# TMS1_2025_NOT_INVERTED.net
KiCad netlist of a schematic drawn in EasyEDA
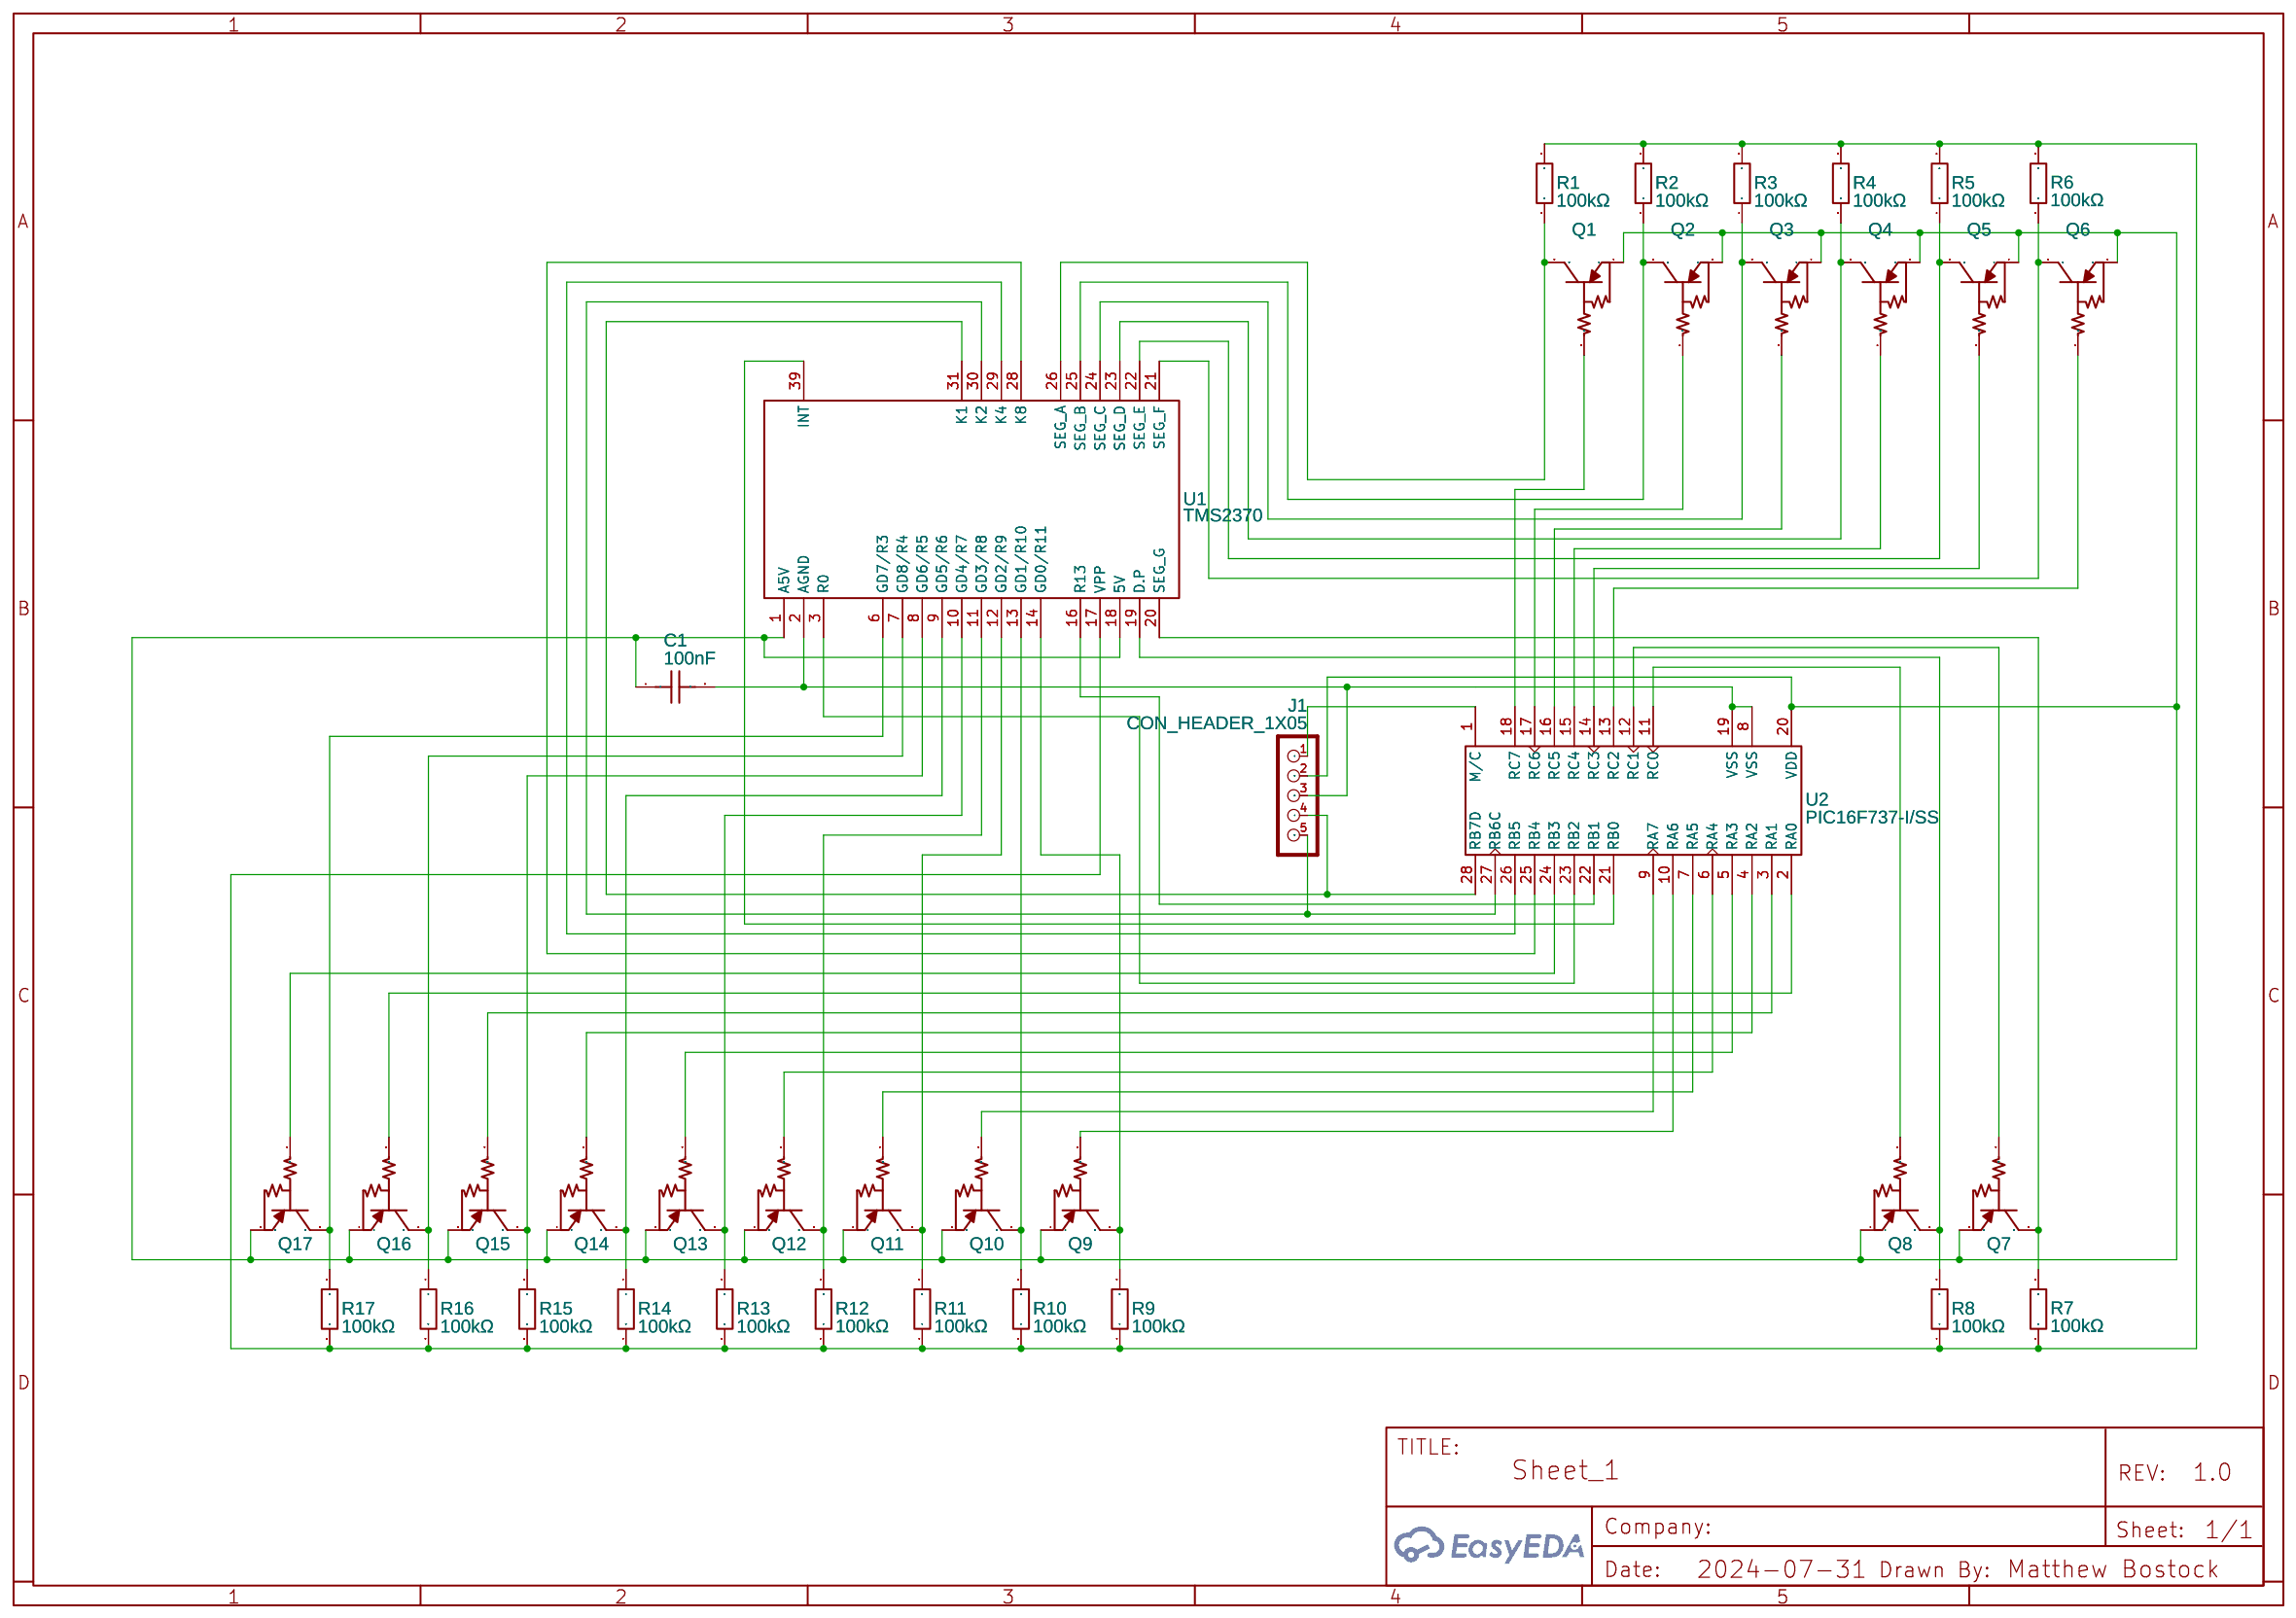
[diagram p0: schematic sheet]

(export (version "E")
  (design (tool "Eeschema 10.0.6"))
  (components
    (comp (ref "C1")
      (value "100nF")
      (fields
        (field (name "Manufacturer Part") "CC0603KRX7R9BB104")
        (field (name "Manufacturer") "YAGEO(国巨)")
      )
      (libsource (lib "") (part "CC0603KRX7R9BB104"))
    )
    (comp (ref "J1") (value "CON_HEADER_1X05") (libsource (lib "") (part "CON_HEADER_1X05")))
    (comp (ref "Q1")
      (value "DTB113ZKT146_SLIM")
      (fields (field (name "Manufacturer Part") "DTB113ZKT146") (field (name "Manufacturer") "ROHM(罗姆)"))
      (libsource (lib "") (part "DTB113ZKT146_SLIM"))
    )
    (comp (ref "Q2")
      (value "DTB113ZKT146_SLIM")
      (fields (field (name "Manufacturer Part") "DTB113ZKT146") (field (name "Manufacturer") "ROHM(罗姆)"))
      (libsource (lib "") (part "DTB113ZKT146_SLIM"))
    )
    (comp (ref "Q3")
      (value "DTB113ZKT146_SLIM")
      (fields (field (name "Manufacturer Part") "DTB113ZKT146") (field (name "Manufacturer") "ROHM(罗姆)"))
      (libsource (lib "") (part "DTB113ZKT146_SLIM"))
    )
    (comp (ref "Q4")
      (value "DTB113ZKT146_SLIM")
      (fields (field (name "Manufacturer Part") "DTB113ZKT146") (field (name "Manufacturer") "ROHM(罗姆)"))
      (libsource (lib "") (part "DTB113ZKT146_SLIM"))
    )
    (comp (ref "Q5")
      (value "DTB113ZKT146_SLIM")
      (fields (field (name "Manufacturer Part") "DTB113ZKT146") (field (name "Manufacturer") "ROHM(罗姆)"))
      (libsource (lib "") (part "DTB113ZKT146_SLIM"))
    )
    (comp (ref "Q6")
      (value "DTB113ZKT146_SLIM")
      (fields (field (name "Manufacturer Part") "DTB113ZKT146") (field (name "Manufacturer") "ROHM(罗姆)"))
      (libsource (lib "") (part "DTB113ZKT146_SLIM"))
    )
    (comp (ref "Q7")
      (value "DTB113ZKT146_SLIM")
      (fields (field (name "Manufacturer Part") "DTB113ZKT146") (field (name "Manufacturer") "ROHM(罗姆)"))
      (libsource (lib "") (part "DTB113ZKT146_SLIM_1"))
    )
    (comp (ref "Q8")
      (value "DTB113ZKT146_SLIM")
      (fields (field (name "Manufacturer Part") "DTB113ZKT146") (field (name "Manufacturer") "ROHM(罗姆)"))
      (libsource (lib "") (part "DTB113ZKT146_SLIM_1"))
    )
    (comp (ref "Q9")
      (value "DTB113ZKT146_SLIM")
      (fields (field (name "Manufacturer Part") "DTB113ZKT146") (field (name "Manufacturer") "ROHM(罗姆)"))
      (libsource (lib "") (part "DTB113ZKT146_SLIM_1"))
    )
    (comp (ref "Q10")
      (value "DTB113ZKT146_SLIM")
      (fields (field (name "Manufacturer Part") "DTB113ZKT146") (field (name "Manufacturer") "ROHM(罗姆)"))
      (libsource (lib "") (part "DTB113ZKT146_SLIM_1"))
    )
    (comp (ref "Q11")
      (value "DTB113ZKT146_SLIM")
      (fields (field (name "Manufacturer Part") "DTB113ZKT146") (field (name "Manufacturer") "ROHM(罗姆)"))
      (libsource (lib "") (part "DTB113ZKT146_SLIM_1"))
    )
    (comp (ref "Q12")
      (value "DTB113ZKT146_SLIM")
      (fields (field (name "Manufacturer Part") "DTB113ZKT146") (field (name "Manufacturer") "ROHM(罗姆)"))
      (libsource (lib "") (part "DTB113ZKT146_SLIM_1"))
    )
    (comp (ref "Q13")
      (value "DTB113ZKT146_SLIM")
      (fields (field (name "Manufacturer Part") "DTB113ZKT146") (field (name "Manufacturer") "ROHM(罗姆)"))
      (libsource (lib "") (part "DTB113ZKT146_SLIM_1"))
    )
    (comp (ref "Q14")
      (value "DTB113ZKT146_SLIM")
      (fields (field (name "Manufacturer Part") "DTB113ZKT146") (field (name "Manufacturer") "ROHM(罗姆)"))
      (libsource (lib "") (part "DTB113ZKT146_SLIM_1"))
    )
    (comp (ref "Q15")
      (value "DTB113ZKT146_SLIM")
      (fields (field (name "Manufacturer Part") "DTB113ZKT146") (field (name "Manufacturer") "ROHM(罗姆)"))
      (libsource (lib "") (part "DTB113ZKT146_SLIM_1"))
    )
    (comp (ref "Q16")
      (value "DTB113ZKT146_SLIM")
      (fields (field (name "Manufacturer Part") "DTB113ZKT146") (field (name "Manufacturer") "ROHM(罗姆)"))
      (libsource (lib "") (part "DTB113ZKT146_SLIM_1"))
    )
    (comp (ref "Q17")
      (value "DTB113ZKT146_SLIM")
      (fields (field (name "Manufacturer Part") "DTB113ZKT146") (field (name "Manufacturer") "ROHM(罗姆)"))
      (libsource (lib "") (part "DTB113ZKT146_SLIM_1"))
    )
    (comp (ref "R1")
      (value "100kΩ")
      (fields (field (name "Manufacturer Part") "RC0603FR-07100KL") (field (name "Manufacturer") "YAGEO(国巨)"))
      (libsource (lib "") (part "RC0603FR-07100KL"))
    )
    (comp (ref "R2")
      (value "100kΩ")
      (fields (field (name "Manufacturer Part") "RC0603FR-07100KL") (field (name "Manufacturer") "YAGEO(国巨)"))
      (libsource (lib "") (part "RC0603FR-07100KL"))
    )
    (comp (ref "R3")
      (value "100kΩ")
      (fields (field (name "Manufacturer Part") "RC0603FR-07100KL") (field (name "Manufacturer") "YAGEO(国巨)"))
      (libsource (lib "") (part "RC0603FR-07100KL"))
    )
    (comp (ref "R4")
      (value "100kΩ")
      (fields (field (name "Manufacturer Part") "RC0603FR-07100KL") (field (name "Manufacturer") "YAGEO(国巨)"))
      (libsource (lib "") (part "RC0603FR-07100KL"))
    )
    (comp (ref "R5")
      (value "100kΩ")
      (fields (field (name "Manufacturer Part") "RC0603FR-07100KL") (field (name "Manufacturer") "YAGEO(国巨)"))
      (libsource (lib "") (part "RC0603FR-07100KL"))
    )
    (comp (ref "R6")
      (value "100kΩ")
      (fields (field (name "Manufacturer Part") "RC0603FR-07100KL") (field (name "Manufacturer") "YAGEO(国巨)"))
      (libsource (lib "") (part "RC0603FR-07100KL"))
    )
    (comp (ref "R7")
      (value "100kΩ")
      (fields (field (name "Manufacturer Part") "RC0603FR-07100KL") (field (name "Manufacturer") "YAGEO(国巨)"))
      (libsource (lib "") (part "RC0603FR-07100KL"))
    )
    (comp (ref "R8")
      (value "100kΩ")
      (fields (field (name "Manufacturer Part") "RC0603FR-07100KL") (field (name "Manufacturer") "YAGEO(国巨)"))
      (libsource (lib "") (part "RC0603FR-07100KL"))
    )
    (comp (ref "R9")
      (value "100kΩ")
      (fields (field (name "Manufacturer Part") "RC0603FR-07100KL") (field (name "Manufacturer") "YAGEO(国巨)"))
      (libsource (lib "") (part "RC0603FR-07100KL"))
    )
    (comp (ref "R10")
      (value "100kΩ")
      (fields (field (name "Manufacturer Part") "RC0603FR-07100KL") (field (name "Manufacturer") "YAGEO(国巨)"))
      (libsource (lib "") (part "RC0603FR-07100KL"))
    )
    (comp (ref "R11")
      (value "100kΩ")
      (fields (field (name "Manufacturer Part") "RC0603FR-07100KL") (field (name "Manufacturer") "YAGEO(国巨)"))
      (libsource (lib "") (part "RC0603FR-07100KL"))
    )
    (comp (ref "R12")
      (value "100kΩ")
      (fields (field (name "Manufacturer Part") "RC0603FR-07100KL") (field (name "Manufacturer") "YAGEO(国巨)"))
      (libsource (lib "") (part "RC0603FR-07100KL"))
    )
    (comp (ref "R13")
      (value "100kΩ")
      (fields (field (name "Manufacturer Part") "RC0603FR-07100KL") (field (name "Manufacturer") "YAGEO(国巨)"))
      (libsource (lib "") (part "RC0603FR-07100KL_1"))
    )
    (comp (ref "R14")
      (value "100kΩ")
      (fields (field (name "Manufacturer Part") "RC0603FR-07100KL") (field (name "Manufacturer") "YAGEO(国巨)"))
      (libsource (lib "") (part "RC0603FR-07100KL_1"))
    )
    (comp (ref "R15")
      (value "100kΩ")
      (fields (field (name "Manufacturer Part") "RC0603FR-07100KL") (field (name "Manufacturer") "YAGEO(国巨)"))
      (libsource (lib "") (part "RC0603FR-07100KL_1"))
    )
    (comp (ref "R16")
      (value "100kΩ")
      (fields (field (name "Manufacturer Part") "RC0603FR-07100KL") (field (name "Manufacturer") "YAGEO(国巨)"))
      (libsource (lib "") (part "RC0603FR-07100KL_1"))
    )
    (comp (ref "R17")
      (value "100kΩ")
      (fields (field (name "Manufacturer Part") "RC0603FR-07100KL") (field (name "Manufacturer") "YAGEO(国巨)"))
      (libsource (lib "") (part "RC0603FR-07100KL_1"))
    )
    (comp (ref "U1")
      (value "TMS2370")
      (fields (field (name "Manufacturer") "Texas Instruments"))
      (libsource (lib "") (part "TMS2370"))
    )
    (comp (ref "U2")
      (value "PIC16F737-I/SS")
      (fields
        (field (name "Manufacturer Part") "PIC16F737-I/SO")
        (field (name "Manufacturer") "MICROCHIP(美国微芯)")
      )
      (libsource (lib "") (part "PIC16F737-I/SO_SLIM"))
    )
  )
  (nets
    (net (code "1") (name "Net-(Q1-B)") (class "Default")
      (node (ref "Q1") (pin "2") (pinfunction "B_2") (pintype "unspecified"))
      (node (ref "U2") (pin "18") (pinfunction "RC7_18") (pintype "unspecified"))
    )
    (net (code "2") (name "Net-(Q1-C)") (class "Default")
      (node (ref "Q1") (pin "3") (pinfunction "C_3") (pintype "unspecified"))
      (node (ref "R1") (pin "1") (pinfunction "1_1") (pintype "unspecified"))
      (node (ref "U1") (pin "26") (pinfunction "SEG_A_26") (pintype "unspecified"))
    )
    (net (code "3") (name "Net-(Q1-E)") (class "Default")
      (node (ref "C1") (pin "1") (pinfunction "1_1") (pintype "unspecified"))
      (node (ref "J1") (pin "2") (pinfunction "2_2") (pintype "unspecified"))
      (node (ref "Q1") (pin "1") (pinfunction "E_1") (pintype "unspecified"))
      (node (ref "Q10") (pin "1") (pinfunction "E_1") (pintype "unspecified"))
      (node (ref "Q11") (pin "1") (pinfunction "E_1") (pintype "unspecified"))
      (node (ref "Q12") (pin "1") (pinfunction "E_1") (pintype "unspecified"))
      (node (ref "Q13") (pin "1") (pinfunction "E_1") (pintype "unspecified"))
      (node (ref "Q14") (pin "1") (pinfunction "E_1") (pintype "unspecified"))
      (node (ref "Q15") (pin "1") (pinfunction "E_1") (pintype "unspecified"))
      (node (ref "Q16") (pin "1") (pinfunction "E_1") (pintype "unspecified"))
      (node (ref "Q17") (pin "1") (pinfunction "E_1") (pintype "unspecified"))
      (node (ref "Q2") (pin "1") (pinfunction "E_1") (pintype "unspecified"))
      (node (ref "Q3") (pin "1") (pinfunction "E_1") (pintype "unspecified"))
      (node (ref "Q4") (pin "1") (pinfunction "E_1") (pintype "unspecified"))
      (node (ref "Q5") (pin "1") (pinfunction "E_1") (pintype "unspecified"))
      (node (ref "Q6") (pin "1") (pinfunction "E_1") (pintype "unspecified"))
      (node (ref "Q7") (pin "1") (pinfunction "E_1") (pintype "unspecified"))
      (node (ref "Q8") (pin "1") (pinfunction "E_1") (pintype "unspecified"))
      (node (ref "Q9") (pin "1") (pinfunction "E_1") (pintype "unspecified"))
      (node (ref "U1") (pin "1") (pinfunction "A5V_1") (pintype "unspecified"))
      (node (ref "U1") (pin "18") (pinfunction "5V_18") (pintype "unspecified"))
      (node (ref "U2") (pin "20") (pinfunction "VDD_20") (pintype "unspecified"))
    )
    (net (code "4") (name "Net-(Q2-B)") (class "Default")
      (node (ref "Q2") (pin "2") (pinfunction "B_2") (pintype "unspecified"))
      (node (ref "U2") (pin "17") (pinfunction "RC6_17") (pintype "unspecified"))
    )
    (net (code "5") (name "Net-(Q2-C)") (class "Default")
      (node (ref "Q2") (pin "3") (pinfunction "C_3") (pintype "unspecified"))
      (node (ref "R2") (pin "1") (pinfunction "1_1") (pintype "unspecified"))
      (node (ref "U1") (pin "25") (pinfunction "SEG_B_25") (pintype "unspecified"))
    )
    (net (code "6") (name "Net-(Q3-B)") (class "Default")
      (node (ref "Q3") (pin "2") (pinfunction "B_2") (pintype "unspecified"))
      (node (ref "U2") (pin "16") (pinfunction "RC5_16") (pintype "unspecified"))
    )
    (net (code "7") (name "Net-(Q3-C)") (class "Default")
      (node (ref "Q3") (pin "3") (pinfunction "C_3") (pintype "unspecified"))
      (node (ref "R3") (pin "1") (pinfunction "1_1") (pintype "unspecified"))
      (node (ref "U1") (pin "24") (pinfunction "SEG_C_24") (pintype "unspecified"))
    )
    (net (code "8") (name "Net-(Q4-B)") (class "Default")
      (node (ref "Q4") (pin "2") (pinfunction "B_2") (pintype "unspecified"))
      (node (ref "U2") (pin "15") (pinfunction "RC4_15") (pintype "unspecified"))
    )
    (net (code "9") (name "Net-(Q4-C)") (class "Default")
      (node (ref "Q4") (pin "3") (pinfunction "C_3") (pintype "unspecified"))
      (node (ref "R4") (pin "1") (pinfunction "1_1") (pintype "unspecified"))
      (node (ref "U1") (pin "23") (pinfunction "SEG_D_23") (pintype "unspecified"))
    )
    (net (code "10") (name "Net-(Q5-B)") (class "Default")
      (node (ref "Q5") (pin "2") (pinfunction "B_2") (pintype "unspecified"))
      (node (ref "U2") (pin "14") (pinfunction "RC3_14") (pintype "unspecified"))
    )
    (net (code "11") (name "Net-(Q5-C)") (class "Default")
      (node (ref "Q5") (pin "3") (pinfunction "C_3") (pintype "unspecified"))
      (node (ref "R5") (pin "1") (pinfunction "1_1") (pintype "unspecified"))
      (node (ref "U1") (pin "22") (pinfunction "SEG_E_22") (pintype "unspecified"))
    )
    (net (code "12") (name "Net-(Q6-B)") (class "Default")
      (node (ref "Q6") (pin "2") (pinfunction "B_2") (pintype "unspecified"))
      (node (ref "U2") (pin "13") (pinfunction "RC2_13") (pintype "unspecified"))
    )
    (net (code "13") (name "Net-(Q6-C)") (class "Default")
      (node (ref "Q6") (pin "3") (pinfunction "C_3") (pintype "unspecified"))
      (node (ref "R6") (pin "1") (pinfunction "1_1") (pintype "unspecified"))
      (node (ref "U1") (pin "21") (pinfunction "SEG_F_21") (pintype "unspecified"))
    )
    (net (code "14") (name "Net-(Q7-B)") (class "Default")
      (node (ref "Q7") (pin "2") (pinfunction "B_2") (pintype "unspecified"))
      (node (ref "U2") (pin "12") (pinfunction "RC1_12") (pintype "unspecified"))
    )
    (net (code "15") (name "Net-(Q7-C)") (class "Default")
      (node (ref "Q7") (pin "3") (pinfunction "C_3") (pintype "unspecified"))
      (node (ref "R7") (pin "2") (pinfunction "2_2") (pintype "unspecified"))
      (node (ref "U1") (pin "20") (pinfunction "SEG_G_20") (pintype "unspecified"))
    )
    (net (code "16") (name "Net-(Q8-B)") (class "Default")
      (node (ref "Q8") (pin "2") (pinfunction "B_2") (pintype "unspecified"))
      (node (ref "U2") (pin "11") (pinfunction "RC0_11") (pintype "unspecified"))
    )
    (net (code "17") (name "Net-(Q8-C)") (class "Default")
      (node (ref "Q8") (pin "3") (pinfunction "C_3") (pintype "unspecified"))
      (node (ref "R8") (pin "2") (pinfunction "2_2") (pintype "unspecified"))
      (node (ref "U1") (pin "19") (pinfunction "D.P_19") (pintype "unspecified"))
    )
    (net (code "18") (name "Net-(Q9-B)") (class "Default")
      (node (ref "Q9") (pin "2") (pinfunction "B_2") (pintype "unspecified"))
      (node (ref "U2") (pin "10") (pinfunction "RA6_10") (pintype "unspecified"))
    )
    (net (code "19") (name "Net-(Q9-C)") (class "Default")
      (node (ref "Q9") (pin "3") (pinfunction "C_3") (pintype "unspecified"))
      (node (ref "R9") (pin "2") (pinfunction "2_2") (pintype "unspecified"))
      (node (ref "U1") (pin "14") (pinfunction "GD0/R11_14") (pintype "unspecified"))
    )
    (net (code "20") (name "Net-(Q10-B)") (class "Default")
      (node (ref "Q10") (pin "2") (pinfunction "B_2") (pintype "unspecified"))
      (node (ref "U2") (pin "9") (pinfunction "RA7_9") (pintype "unspecified"))
    )
    (net (code "21") (name "Net-(Q10-C)") (class "Default")
      (node (ref "Q10") (pin "3") (pinfunction "C_3") (pintype "unspecified"))
      (node (ref "R10") (pin "2") (pinfunction "2_2") (pintype "unspecified"))
      (node (ref "U1") (pin "13") (pinfunction "GD1/R10_13") (pintype "unspecified"))
    )
    (net (code "22") (name "Net-(Q11-B)") (class "Default")
      (node (ref "Q11") (pin "2") (pinfunction "B_2") (pintype "unspecified"))
      (node (ref "U2") (pin "7") (pinfunction "RA5_7") (pintype "unspecified"))
    )
    (net (code "23") (name "Net-(Q11-C)") (class "Default")
      (node (ref "Q11") (pin "3") (pinfunction "C_3") (pintype "unspecified"))
      (node (ref "R11") (pin "2") (pinfunction "2_2") (pintype "unspecified"))
      (node (ref "U1") (pin "12") (pinfunction "GD2/R9_12") (pintype "unspecified"))
    )
    (net (code "24") (name "Net-(Q12-B)") (class "Default")
      (node (ref "Q12") (pin "2") (pinfunction "B_2") (pintype "unspecified"))
      (node (ref "U2") (pin "6") (pinfunction "RA4_6") (pintype "unspecified"))
    )
    (net (code "25") (name "Net-(Q12-C)") (class "Default")
      (node (ref "Q12") (pin "3") (pinfunction "C_3") (pintype "unspecified"))
      (node (ref "R12") (pin "2") (pinfunction "2_2") (pintype "unspecified"))
      (node (ref "U1") (pin "11") (pinfunction "GD3/R8_11") (pintype "unspecified"))
    )
    (net (code "26") (name "Net-(Q13-B)") (class "Default")
      (node (ref "Q13") (pin "2") (pinfunction "B_2") (pintype "unspecified"))
      (node (ref "U2") (pin "5") (pinfunction "RA3_5") (pintype "unspecified"))
    )
    (net (code "27") (name "Net-(Q13-C)") (class "Default")
      (node (ref "Q13") (pin "3") (pinfunction "C_3") (pintype "unspecified"))
      (node (ref "R13") (pin "1") (pinfunction "1_1") (pintype "unspecified"))
      (node (ref "U1") (pin "10") (pinfunction "GD4/R7_10") (pintype "unspecified"))
    )
    (net (code "28") (name "Net-(Q14-B)") (class "Default")
      (node (ref "Q14") (pin "2") (pinfunction "B_2") (pintype "unspecified"))
      (node (ref "U2") (pin "4") (pinfunction "RA2_4") (pintype "unspecified"))
    )
    (net (code "29") (name "Net-(Q14-C)") (class "Default")
      (node (ref "Q14") (pin "3") (pinfunction "C_3") (pintype "unspecified"))
      (node (ref "R14") (pin "1") (pinfunction "1_1") (pintype "unspecified"))
      (node (ref "U1") (pin "9") (pinfunction "GD5/R6_9") (pintype "unspecified"))
    )
    (net (code "30") (name "Net-(Q15-B)") (class "Default")
      (node (ref "Q15") (pin "2") (pinfunction "B_2") (pintype "unspecified"))
      (node (ref "U2") (pin "3") (pinfunction "RA1_3") (pintype "unspecified"))
    )
    (net (code "31") (name "Net-(Q15-C)") (class "Default")
      (node (ref "Q15") (pin "3") (pinfunction "C_3") (pintype "unspecified"))
      (node (ref "R15") (pin "1") (pinfunction "1_1") (pintype "unspecified"))
      (node (ref "U1") (pin "8") (pinfunction "GD6/R5_8") (pintype "unspecified"))
    )
    (net (code "32") (name "Net-(Q16-B)") (class "Default")
      (node (ref "Q16") (pin "2") (pinfunction "B_2") (pintype "unspecified"))
      (node (ref "U2") (pin "2") (pinfunction "RA0_2") (pintype "unspecified"))
    )
    (net (code "33") (name "Net-(Q16-C)") (class "Default")
      (node (ref "Q16") (pin "3") (pinfunction "C_3") (pintype "unspecified"))
      (node (ref "R16") (pin "1") (pinfunction "1_1") (pintype "unspecified"))
      (node (ref "U1") (pin "7") (pinfunction "GD8/R4_7") (pintype "unspecified"))
    )
    (net (code "34") (name "Net-(Q17-B)") (class "Default")
      (node (ref "Q17") (pin "2") (pinfunction "B_2") (pintype "unspecified"))
      (node (ref "U2") (pin "24") (pinfunction "RB3_24") (pintype "unspecified"))
    )
    (net (code "35") (name "Net-(Q17-C)") (class "Default")
      (node (ref "Q17") (pin "3") (pinfunction "C_3") (pintype "unspecified"))
      (node (ref "R17") (pin "1") (pinfunction "1_1") (pintype "unspecified"))
      (node (ref "U1") (pin "6") (pinfunction "GD7/R3_6") (pintype "unspecified"))
    )
    (net (code "36") (name "Net-(U1-AGND)") (class "Default")
      (node (ref "C1") (pin "2") (pinfunction "2_2") (pintype "unspecified"))
      (node (ref "J1") (pin "3") (pinfunction "3_3") (pintype "unspecified"))
      (node (ref "U1") (pin "2") (pinfunction "AGND_2") (pintype "unspecified"))
      (node (ref "U2") (pin "19") (pinfunction "VSS_19") (pintype "unspecified"))
      (node (ref "U2") (pin "8") (pinfunction "VSS_8") (pintype "unspecified"))
    )
    (net (code "37") (name "Net-(U1-INT)") (class "Default")
      (node (ref "U1") (pin "39") (pinfunction "INT_39") (pintype "unspecified"))
      (node (ref "U2") (pin "21") (pinfunction "RB0_21") (pintype "unspecified"))
    )
    (net (code "38") (name "Net-(U1-K1)") (class "Default")
      (node (ref "J1") (pin "4") (pinfunction "4_4") (pintype "unspecified"))
      (node (ref "U1") (pin "31") (pinfunction "K1_31") (pintype "unspecified"))
      (node (ref "U2") (pin "28") (pinfunction "RB7D_28") (pintype "unspecified"))
    )
    (net (code "39") (name "Net-(U1-K2)") (class "Default")
      (node (ref "J1") (pin "5") (pinfunction "5_5") (pintype "unspecified"))
      (node (ref "U1") (pin "30") (pinfunction "K2_30") (pintype "unspecified"))
      (node (ref "U2") (pin "27") (pinfunction "RB6C_27") (pintype "unspecified"))
    )
    (net (code "40") (name "Net-(U1-K4)") (class "Default")
      (node (ref "U1") (pin "29") (pinfunction "K4_29") (pintype "unspecified"))
      (node (ref "U2") (pin "26") (pinfunction "RB5_26") (pintype "unspecified"))
    )
    (net (code "41") (name "Net-(U1-K8)") (class "Default")
      (node (ref "U1") (pin "28") (pinfunction "K8_28") (pintype "unspecified"))
      (node (ref "U2") (pin "25") (pinfunction "RB4_25") (pintype "unspecified"))
    )
    (net (code "42") (name "Net-(U1-R0)") (class "Default")
      (node (ref "U1") (pin "3") (pinfunction "R0_3") (pintype "unspecified"))
      (node (ref "U2") (pin "23") (pinfunction "RB2_23") (pintype "unspecified"))
    )
    (net (code "43") (name "Net-(U1-R13)") (class "Default")
      (node (ref "U1") (pin "16") (pinfunction "R13_16") (pintype "unspecified"))
      (node (ref "U2") (pin "22") (pinfunction "RB1_22") (pintype "unspecified"))
    )
    (net (code "44") (name "Net-(U1-VPP)") (class "Default")
      (node (ref "R1") (pin "2") (pinfunction "2_2") (pintype "unspecified"))
      (node (ref "R10") (pin "1") (pinfunction "1_1") (pintype "unspecified"))
      (node (ref "R11") (pin "1") (pinfunction "1_1") (pintype "unspecified"))
      (node (ref "R12") (pin "1") (pinfunction "1_1") (pintype "unspecified"))
      (node (ref "R13") (pin "2") (pinfunction "2_2") (pintype "unspecified"))
      (node (ref "R14") (pin "2") (pinfunction "2_2") (pintype "unspecified"))
      (node (ref "R15") (pin "2") (pinfunction "2_2") (pintype "unspecified"))
      (node (ref "R16") (pin "2") (pinfunction "2_2") (pintype "unspecified"))
      (node (ref "R17") (pin "2") (pinfunction "2_2") (pintype "unspecified"))
      (node (ref "R2") (pin "2") (pinfunction "2_2") (pintype "unspecified"))
      (node (ref "R3") (pin "2") (pinfunction "2_2") (pintype "unspecified"))
      (node (ref "R4") (pin "2") (pinfunction "2_2") (pintype "unspecified"))
      (node (ref "R5") (pin "2") (pinfunction "2_2") (pintype "unspecified"))
      (node (ref "R6") (pin "2") (pinfunction "2_2") (pintype "unspecified"))
      (node (ref "R7") (pin "1") (pinfunction "1_1") (pintype "unspecified"))
      (node (ref "R8") (pin "1") (pinfunction "1_1") (pintype "unspecified"))
      (node (ref "R9") (pin "1") (pinfunction "1_1") (pintype "unspecified"))
      (node (ref "U1") (pin "17") (pinfunction "VPP_17") (pintype "unspecified"))
    )
    (net (code "45") (name "Net-(U2-M{slash}C)") (class "Default")
      (node (ref "J1") (pin "1") (pinfunction "1_1") (pintype "unspecified"))
      (node (ref "U2") (pin "1") (pinfunction "M/C_1") (pintype "unspecified"))
    )
  )
)
